# PowerToSer.net
KiCad netlist of a schematic drawn in Altium Designer
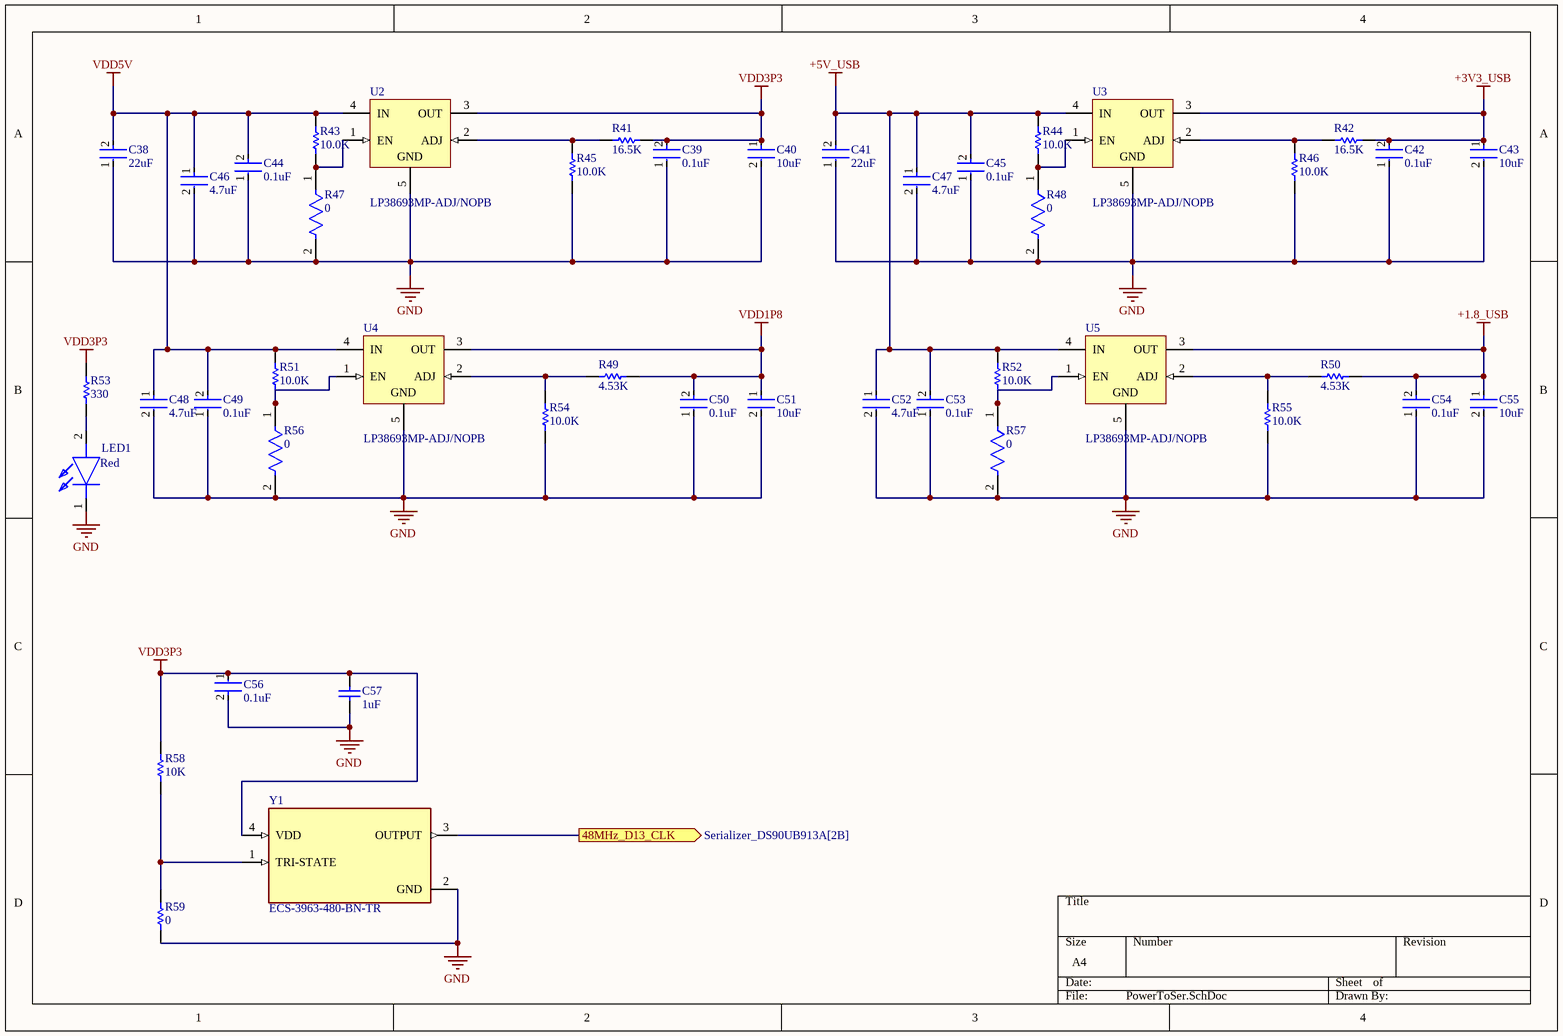
[diagram p0: PowerToSer.SchDoc]

(export (version "E")
  (design (tool "Eeschema 10.0.6"))
  (components
    (comp (ref "C38")
      (value "22uF")
      (footprint "FP-GCM32E-0_3-IPC_B")
      (description "Ceramic Capacitor for Automotive 22uF ±10% 16VDC X7R 1210 Embossed T/R")
      (fields (field (name "VOLTAGE") "16V") (field (name "TOLERANCE") "10%"))
      (libsource (lib "Altium Content Vault") (part "f23184f103b6ebe33a8c269c53dcba6"))
    )
    (comp (ref "C39")
      (value "0.1uF")
      (footprint "FP-GRM15-MFG")
      (description "CAP CER 0.1UF 16V X7R 0402")
      (fields (field (name "MANUFACTURER PART NUMBER") "GRM155R71C104KA88D") (field (name "TOLERANCE") "10%"))
      (libsource (lib "Altium Content Vault") (part "236180d848d6139a670b325ea6854c9"))
    )
    (comp (ref "C40")
      (value "10uF")
      (footprint "FP-GRM21B-0_1-IPC_C")
      (description "Chip Multilayer Ceramic Capacitors for General Purpose, 0805, 10uF, X5R, 15%, 10%, 16V")
      (fields (field (name "TOLERANCE") "10%") (field (name "VOLTAGE") "16V"))
      (libsource (lib "Altium Content Vault") (part "b4654b650e69147ec39a6b967a45e02"))
    )
    (comp (ref "C41")
      (value "22uF")
      (footprint "FP-GCM32E-0_3-IPC_B")
      (description "Ceramic Capacitor for Automotive 22uF ±10% 16VDC X7R 1210 Embossed T/R")
      (fields (field (name "VOLTAGE") "16V") (field (name "TOLERANCE") "10%"))
      (libsource (lib "Altium Content Vault") (part "f23184f103b6ebe33a8c269c53dcba6"))
    )
    (comp (ref "C42")
      (value "0.1uF")
      (footprint "FP-GRM15-MFG")
      (description "CAP CER 0.1UF 16V X7R 0402")
      (fields (field (name "MANUFACTURER PART NUMBER") "GRM155R71C104KA88D") (field (name "TOLERANCE") "10%"))
      (libsource (lib "Altium Content Vault") (part "236180d848d6139a670b325ea6854c9"))
    )
    (comp (ref "C43")
      (value "10uF")
      (footprint "FP-GRM21B-0_1-IPC_C")
      (description "Chip Multilayer Ceramic Capacitors for General Purpose, 0805, 10uF, X5R, 15%, 10%, 16V")
      (fields (field (name "TOLERANCE") "10%") (field (name "VOLTAGE") "16V"))
      (libsource (lib "Altium Content Vault") (part "b4654b650e69147ec39a6b967a45e02"))
    )
    (comp (ref "C44")
      (value "0.1uF")
      (footprint "FP-GRM15-MFG")
      (description "CAP CER 0.1UF 16V X7R 0402")
      (fields (field (name "MANUFACTURER PART NUMBER") "GRM155R71C104KA88D") (field (name "TOLERANCE") "10%"))
      (libsource (lib "Altium Content Vault") (part "236180d848d6139a670b325ea6854c9"))
    )
    (comp (ref "C45")
      (value "0.1uF")
      (footprint "FP-GRM15-MFG")
      (description "CAP CER 0.1UF 16V X7R 0402")
      (fields (field (name "MANUFACTURER PART NUMBER") "GRM155R71C104KA88D") (field (name "TOLERANCE") "10%"))
      (libsource (lib "Altium Content Vault") (part "236180d848d6139a670b325ea6854c9"))
    )
    (comp (ref "C46")
      (value "4.7uF")
      (footprint "FP-GRM21B-0_15-MFG")
      (description "CAP CER 4.7UF 16V X7R 0805")
      (fields (field (name "VOLTAGE") "16V") (field (name "TOLERANCE") "10%"))
      (libsource (lib "Altium Content Vault") (part "b4654b650e69147ec39a6b967a45e02"))
    )
    (comp (ref "C47")
      (value "4.7uF")
      (footprint "FP-GRM21B-0_15-MFG")
      (description "CAP CER 4.7UF 16V X7R 0805")
      (fields (field (name "VOLTAGE") "16V") (field (name "TOLERANCE") "10%"))
      (libsource (lib "Altium Content Vault") (part "b4654b650e69147ec39a6b967a45e02"))
    )
    (comp (ref "C48")
      (value "4.7uF")
      (footprint "FP-GRM21B-0_15-MFG")
      (description "CAP CER 4.7UF 16V X7R 0805")
      (fields (field (name "VOLTAGE") "16V") (field (name "TOLERANCE") "10%"))
      (libsource (lib "Altium Content Vault") (part "b4654b650e69147ec39a6b967a45e02"))
    )
    (comp (ref "C49")
      (value "0.1uF")
      (footprint "FP-GRM15-MFG")
      (description "CAP CER 0.1UF 16V X7R 0402")
      (fields (field (name "MANUFACTURER PART NUMBER") "GRM155R71C104KA88D") (field (name "TOLERANCE") "10%"))
      (libsource (lib "Altium Content Vault") (part "236180d848d6139a670b325ea6854c9"))
    )
    (comp (ref "C50")
      (value "0.1uF")
      (footprint "FP-GRM15-MFG")
      (description "CAP CER 0.1UF 16V X7R 0402")
      (fields (field (name "MANUFACTURER PART NUMBER") "GRM155R71C104KA88D") (field (name "TOLERANCE") "10%"))
      (libsource (lib "Altium Content Vault") (part "236180d848d6139a670b325ea6854c9"))
    )
    (comp (ref "C51")
      (value "10uF")
      (footprint "FP-GRM21B-0_1-IPC_C")
      (description "Chip Multilayer Ceramic Capacitors for General Purpose, 0805, 10uF, X5R, 15%, 10%, 16V")
      (fields (field (name "TOLERANCE") "10%") (field (name "VOLTAGE") "16V"))
      (libsource (lib "Altium Content Vault") (part "b4654b650e69147ec39a6b967a45e02"))
    )
    (comp (ref "C52")
      (value "4.7uF")
      (footprint "FP-GRM21B-0_15-MFG")
      (description "CAP CER 4.7UF 16V X7R 0805")
      (fields (field (name "VOLTAGE") "16V") (field (name "TOLERANCE") "10%"))
      (libsource (lib "Altium Content Vault") (part "b4654b650e69147ec39a6b967a45e02"))
    )
    (comp (ref "C53")
      (value "0.1uF")
      (footprint "FP-GRM15-MFG")
      (description "CAP CER 0.1UF 16V X7R 0402")
      (fields (field (name "MANUFACTURER PART NUMBER") "GRM155R71C104KA88D") (field (name "TOLERANCE") "10%"))
      (libsource (lib "Altium Content Vault") (part "236180d848d6139a670b325ea6854c9"))
    )
    (comp (ref "C54")
      (value "0.1uF")
      (footprint "FP-GRM15-MFG")
      (description "CAP CER 0.1UF 16V X7R 0402")
      (fields (field (name "MANUFACTURER PART NUMBER") "GRM155R71C104KA88D") (field (name "TOLERANCE") "10%"))
      (libsource (lib "Altium Content Vault") (part "236180d848d6139a670b325ea6854c9"))
    )
    (comp (ref "C55")
      (value "10uF")
      (footprint "FP-GRM21B-0_1-IPC_C")
      (description "Chip Multilayer Ceramic Capacitors for General Purpose, 0805, 10uF, X5R, 15%, 10%, 16V")
      (fields (field (name "TOLERANCE") "10%") (field (name "VOLTAGE") "16V"))
      (libsource (lib "Altium Content Vault") (part "b4654b650e69147ec39a6b967a45e02"))
    )
    (comp (ref "C56")
      (value "0.1uF")
      (footprint "FP-GRM15-MFG")
      (description "CAP CER 0.1UF 16V X7R 0402")
      (fields (field (name "MANUFACTURER PART NUMBER") "GRM155R71C104KA88D") (field (name "TOLERANCE") "10%"))
      (libsource (lib "Altium Content Vault") (part "236180d848d6139a670b325ea6854c9"))
    )
    (comp (ref "C57")
      (value "1uF")
      (footprint "CAPC1608X90X35ML10T15")
      (fields (field (name "MANUFACTURER") "Murata") (field (name "PART NUMBER") "GRM188R71E105KA12D"))
      (libsource (lib "Altium Content Vault") (part "CAP"))
    )
    (comp (ref "LED1")
      (value "Red")
      (footprint "SerDes_Eval_Board_Footprints:LEDC1608X55N")
      (description "LED")
      (fields
        (field (name "MANUFACTURER_PART_NUMBER") "LTST-C191KRKT")
        (field (name "MOUSER PART NUMBER") "859-LTST-C191KRKT")
      )
      (libsource (lib "SerDes_Eval") (part "LTST-C191KRKT"))
    )
    (comp (ref "R41")
      (value "16.5K")
      (footprint "RESC1608X55X30LL15T15")
      (fields (field (name "MANUFACTURER") "Panasonic") (field (name "PART NUMBER") "ERJ-3EKF1652V"))
      (libsource (lib "Altium Content Vault") (part "RES"))
    )
    (comp (ref "R42")
      (value "16.5K")
      (footprint "RESC1608X55X30LL15T15")
      (fields (field (name "MANUFACTURER") "Panasonic") (field (name "PART NUMBER") "ERJ-3EKF1652V"))
      (libsource (lib "Altium Content Vault") (part "RES"))
    )
    (comp (ref "R43")
      (value "10.0K")
      (footprint "RESC1609X55X30LL15T15")
      (description "Chip Resistor, 10 KOhm, +/- 1%, 0.1 W, -55 to 155 degC, 0603 (1608 Metric), RoHS, Tape and Reel")
      (fields (field (name "TOLERANCE") "1%") (field (name "MANUFACTURER") "Panasonic"))
      (libsource (lib "Altium Content Vault") (part "RES-2"))
    )
    (comp (ref "R44")
      (value "10.0K")
      (footprint "RESC1609X55X30LL15T15")
      (description "Chip Resistor, 10 KOhm, +/- 1%, 0.1 W, -55 to 155 degC, 0603 (1608 Metric), RoHS, Tape and Reel")
      (fields (field (name "TOLERANCE") "1%") (field (name "MANUFACTURER") "Panasonic"))
      (libsource (lib "Altium Content Vault") (part "RES-2"))
    )
    (comp (ref "R45")
      (value "10.0K")
      (footprint "RESC1609X55X30LL15T15")
      (description "Chip Resistor, 10 KOhm, +/- 1%, 0.1 W, -55 to 155 degC, 0603 (1608 Metric), RoHS, Tape and Reel")
      (fields (field (name "TOLERANCE") "1%") (field (name "MANUFACTURER") "Panasonic"))
      (libsource (lib "Altium Content Vault") (part "RES-2"))
    )
    (comp (ref "R46")
      (value "10.0K")
      (footprint "RESC1609X55X30LL15T15")
      (description "Chip Resistor, 10 KOhm, +/- 1%, 0.1 W, -55 to 155 degC, 0603 (1608 Metric), RoHS, Tape and Reel")
      (fields (field (name "TOLERANCE") "1%") (field (name "MANUFACTURER") "Panasonic"))
      (libsource (lib "Altium Content Vault") (part "RES-2"))
    )
    (comp (ref "R47")
      (value "0")
      (footprint "FP-ERJ-3GEY0R00V-MFG")
      (description "RES SMD 0 OHM JUMPER 1/10W 0603")
      (fields (field (name "TOLERANCE") "5%") (field (name "MANUFACTURER PART NUMBER") "ERJ-3GEY0R00V"))
      (libsource (lib "Altium Content Vault") (part "1029c3af85768c4190bb7ad29bc67b5"))
    )
    (comp (ref "R48")
      (value "0")
      (footprint "FP-ERJ-3GEY0R00V-MFG")
      (description "RES SMD 0 OHM JUMPER 1/10W 0603")
      (fields (field (name "TOLERANCE") "5%") (field (name "MANUFACTURER PART NUMBER") "ERJ-3GEY0R00V"))
      (libsource (lib "Altium Content Vault") (part "1029c3af85768c4190bb7ad29bc67b5"))
    )
    (comp (ref "R49")
      (value "4.53K")
      (footprint "RESC1608X55X30ML15T15")
      (fields (field (name "PART NUMBER") "ERJ-3EKF4531V") (field (name "MANUFACTURER") "Panasonic"))
      (libsource (lib "Altium Content Vault") (part "RES"))
    )
    (comp (ref "R50")
      (value "4.53K")
      (footprint "RESC1608X55X30ML15T15")
      (fields (field (name "PART NUMBER") "ERJ-3EKF4531V") (field (name "MANUFACTURER") "Panasonic"))
      (libsource (lib "Altium Content Vault") (part "RES"))
    )
    (comp (ref "R51")
      (value "10.0K")
      (footprint "RESC1609X55X30LL15T15")
      (description "Chip Resistor, 10 KOhm, +/- 1%, 0.1 W, -55 to 155 degC, 0603 (1608 Metric), RoHS, Tape and Reel")
      (fields (field (name "TOLERANCE") "1%") (field (name "MANUFACTURER") "Panasonic"))
      (libsource (lib "Altium Content Vault") (part "RES-2"))
    )
    (comp (ref "R52")
      (value "10.0K")
      (footprint "RESC1609X55X30LL15T15")
      (description "Chip Resistor, 10 KOhm, +/- 1%, 0.1 W, -55 to 155 degC, 0603 (1608 Metric), RoHS, Tape and Reel")
      (fields (field (name "TOLERANCE") "1%") (field (name "MANUFACTURER") "Panasonic"))
      (libsource (lib "Altium Content Vault") (part "RES-2"))
    )
    (comp (ref "R53")
      (value "330")
      (footprint "RESC1005X40X25ML05T05")
      (fields (field (name "MANUFACTURER") "Panasonic") (field (name "PART NUMBER") "ERJ2RKF3300X"))
      (libsource (lib "Altium Content Vault") (part "RES"))
    )
    (comp (ref "R54")
      (value "10.0K")
      (footprint "RESC1609X55X30LL15T15")
      (description "Chip Resistor, 10 KOhm, +/- 1%, 0.1 W, -55 to 155 degC, 0603 (1608 Metric), RoHS, Tape and Reel")
      (fields (field (name "TOLERANCE") "1%") (field (name "MANUFACTURER") "Panasonic"))
      (libsource (lib "Altium Content Vault") (part "RES-2"))
    )
    (comp (ref "R55")
      (value "10.0K")
      (footprint "RESC1609X55X30LL15T15")
      (description "Chip Resistor, 10 KOhm, +/- 1%, 0.1 W, -55 to 155 degC, 0603 (1608 Metric), RoHS, Tape and Reel")
      (fields (field (name "TOLERANCE") "1%") (field (name "MANUFACTURER") "Panasonic"))
      (libsource (lib "Altium Content Vault") (part "RES-2"))
    )
    (comp (ref "R56")
      (value "0")
      (footprint "FP-ERJ-3GEY0R00V-MFG")
      (description "RES SMD 0 OHM JUMPER 1/10W 0603")
      (fields (field (name "TOLERANCE") "5%") (field (name "MANUFACTURER PART NUMBER") "ERJ-3GEY0R00V"))
      (libsource (lib "Altium Content Vault") (part "1029c3af85768c4190bb7ad29bc67b5"))
    )
    (comp (ref "R57")
      (value "0")
      (footprint "FP-ERJ-3GEY0R00V-MFG")
      (description "RES SMD 0 OHM JUMPER 1/10W 0603")
      (fields (field (name "TOLERANCE") "5%") (field (name "MANUFACTURER PART NUMBER") "ERJ-3GEY0R00V"))
      (libsource (lib "Altium Content Vault") (part "1029c3af85768c4190bb7ad29bc67b5"))
    )
    (comp (ref "R58")
      (value "10K")
      (footprint "RESC1005X40X25ML05T05")
      (fields (field (name "PART NUMBER") "ERJ-2GEJ103X") (field (name "MANUFACTURER") "Panasonic"))
      (libsource (lib "Altium Content Vault") (part "RES"))
    )
    (comp (ref "R59")
      (value "0")
      (footprint "RESC1005X40X25LL05T05")
      (description "Chip Resistor, 0 Ohm, 0.1 W, -55 to 155 degC, 0402 (1005 Metric), RoHS, Tape and Reel")
      (fields (field (name "MANUFACTURER") "Panasonic") (field (name "TOLERANCE") "5%"))
      (libsource (lib "Altium Content Vault") (part "RES-2"))
    )
    (comp (ref "U2")
      (value "LP38693MP-ADJ/NOPB")
      (footprint "NDC0005A_N")
      (fields (field (name "MANUFACTURER") "Texas Instruments"))
      (libsource (lib "Altium Content Vault") (part "PM-REG-LP38693ADJ-SOT5"))
    )
    (comp (ref "U3")
      (value "LP38693MP-ADJ/NOPB")
      (footprint "NDC0005A_N")
      (fields (field (name "MANUFACTURER") "Texas Instruments"))
      (libsource (lib "Altium Content Vault") (part "PM-REG-LP38693ADJ-SOT5"))
    )
    (comp (ref "U4")
      (value "LP38693MP-ADJ/NOPB")
      (footprint "NDC0005A_N")
      (fields (field (name "MANUFACTURER") "Texas Instruments"))
      (libsource (lib "Altium Content Vault") (part "PM-REG-LP38693ADJ-SOT5"))
    )
    (comp (ref "U5")
      (value "LP38693MP-ADJ/NOPB")
      (footprint "NDC0005A_N")
      (fields (field (name "MANUFACTURER") "Texas Instruments"))
      (libsource (lib "Altium Content Vault") (part "PM-REG-LP38693ADJ-SOT5"))
    )
    (comp (ref "Y1")
      (value "ECS-3963-480-BN-TR")
      (footprint "SerDes_Eval_Board_Footprints:OSC_ECS-3963-480-BN-TR")
      (description "miniature SMD crystal controlled oscillators")
      (libsource (lib "SerDes_Eval") (part "ECS-3963-480-BN-TR"))
    )
  )
  (nets
    (net (code "1") (name "+1.8_USB") (class "Default")
      (node (ref "C54") (pin "2") (pinfunction "2_2") (pintype "passive"))
      (node (ref "C55") (pin "1") (pinfunction "1_1") (pintype "passive"))
      (node (ref "R50") (pin "2") (pinfunction "2_2") (pintype "passive"))
      (node (ref "U5") (pin "3") (pinfunction "OUT_3") (pintype "power_in"))
    )
    (net (code "2") (name "+3V3_USB") (class "Default")
      (node (ref "C42") (pin "2") (pinfunction "2_2") (pintype "passive"))
      (node (ref "C43") (pin "1") (pinfunction "1_1") (pintype "passive"))
      (node (ref "R42") (pin "2") (pinfunction "2_2") (pintype "passive"))
      (node (ref "U3") (pin "3") (pinfunction "OUT_3") (pintype "power_in"))
    )
    (net (code "3") (name "+5V_USB") (class "Default")
      (node (ref "C41") (pin "2") (pinfunction "2_2") (pintype "passive"))
      (node (ref "C45") (pin "2") (pinfunction "2_2") (pintype "passive"))
      (node (ref "C47") (pin "1") (pinfunction "1_1") (pintype "passive"))
      (node (ref "C52") (pin "1") (pinfunction "1_1") (pintype "passive"))
      (node (ref "C53") (pin "2") (pinfunction "2_2") (pintype "passive"))
      (node (ref "R44") (pin "1") (pinfunction "1_1") (pintype "passive"))
      (node (ref "R52") (pin "1") (pinfunction "1_1") (pintype "passive"))
      (node (ref "U3") (pin "4") (pinfunction "IN_4") (pintype "power_in"))
      (node (ref "U5") (pin "4") (pinfunction "IN_4") (pintype "power_in"))
    )
    (net (code "4") (name "/48MHz_D13_CLK") (class "Default")
      (node (ref "Y1") (pin "3") (pinfunction "OUTPUT_3") (pintype "output"))
    )
    (net (code "5") (name "GND") (class "Default")
      (node (ref "C38") (pin "1") (pinfunction "1_1") (pintype "passive"))
      (node (ref "C39") (pin "1") (pinfunction "1_1") (pintype "passive"))
      (node (ref "C40") (pin "2") (pinfunction "2_2") (pintype "passive"))
      (node (ref "C41") (pin "1") (pinfunction "1_1") (pintype "passive"))
      (node (ref "C42") (pin "1") (pinfunction "1_1") (pintype "passive"))
      (node (ref "C43") (pin "2") (pinfunction "2_2") (pintype "passive"))
      (node (ref "C44") (pin "1") (pinfunction "1_1") (pintype "passive"))
      (node (ref "C45") (pin "1") (pinfunction "1_1") (pintype "passive"))
      (node (ref "C46") (pin "2") (pinfunction "2_2") (pintype "passive"))
      (node (ref "C47") (pin "2") (pinfunction "2_2") (pintype "passive"))
      (node (ref "C48") (pin "2") (pinfunction "2_2") (pintype "passive"))
      (node (ref "C49") (pin "1") (pinfunction "1_1") (pintype "passive"))
      (node (ref "C50") (pin "1") (pinfunction "1_1") (pintype "passive"))
      (node (ref "C51") (pin "2") (pinfunction "2_2") (pintype "passive"))
      (node (ref "C52") (pin "2") (pinfunction "2_2") (pintype "passive"))
      (node (ref "C53") (pin "1") (pinfunction "1_1") (pintype "passive"))
      (node (ref "C54") (pin "1") (pinfunction "1_1") (pintype "passive"))
      (node (ref "C55") (pin "2") (pinfunction "2_2") (pintype "passive"))
      (node (ref "C56") (pin "2") (pinfunction "2_2") (pintype "passive"))
      (node (ref "C57") (pin "2") (pinfunction "2_2") (pintype "passive"))
      (node (ref "LED1") (pin "1") (pinfunction "K_1") (pintype "passive"))
      (node (ref "R45") (pin "2") (pinfunction "2_2") (pintype "passive"))
      (node (ref "R46") (pin "2") (pinfunction "2_2") (pintype "passive"))
      (node (ref "R47") (pin "2") (pinfunction "2_2") (pintype "passive"))
      (node (ref "R48") (pin "2") (pinfunction "2_2") (pintype "passive"))
      (node (ref "R54") (pin "2") (pinfunction "2_2") (pintype "passive"))
      (node (ref "R55") (pin "2") (pinfunction "2_2") (pintype "passive"))
      (node (ref "R56") (pin "2") (pinfunction "2_2") (pintype "passive"))
      (node (ref "R57") (pin "2") (pinfunction "2_2") (pintype "passive"))
      (node (ref "R59") (pin "2") (pinfunction "2_2") (pintype "passive"))
      (node (ref "U2") (pin "5") (pinfunction "GND_5") (pintype "power_in"))
      (node (ref "U3") (pin "5") (pinfunction "GND_5") (pintype "power_in"))
      (node (ref "U4") (pin "5") (pinfunction "GND_5") (pintype "power_in"))
      (node (ref "U5") (pin "5") (pinfunction "GND_5") (pintype "power_in"))
      (node (ref "Y1") (pin "2") (pinfunction "GND_2") (pintype "power_in"))
    )
    (net (code "6") (name "Net-(LED1-A)") (class "Default")
      (node (ref "LED1") (pin "2") (pinfunction "A_2") (pintype "passive"))
      (node (ref "R53") (pin "2") (pinfunction "2_2") (pintype "passive"))
    )
    (net (code "7") (name "Net-(U2-ADJ)") (class "Default")
      (node (ref "R41") (pin "1") (pinfunction "1_1") (pintype "passive"))
      (node (ref "R45") (pin "1") (pinfunction "1_1") (pintype "passive"))
      (node (ref "U2") (pin "2") (pinfunction "ADJ_2") (pintype "input"))
    )
    (net (code "8") (name "Net-(U2-EN)") (class "Default")
      (node (ref "R43") (pin "2") (pinfunction "2_2") (pintype "passive"))
      (node (ref "R47") (pin "1") (pinfunction "1_1") (pintype "passive"))
      (node (ref "U2") (pin "1") (pinfunction "EN_1") (pintype "input"))
    )
    (net (code "9") (name "Net-(U3-ADJ)") (class "Default")
      (node (ref "R42") (pin "1") (pinfunction "1_1") (pintype "passive"))
      (node (ref "R46") (pin "1") (pinfunction "1_1") (pintype "passive"))
      (node (ref "U3") (pin "2") (pinfunction "ADJ_2") (pintype "input"))
    )
    (net (code "10") (name "Net-(U3-EN)") (class "Default")
      (node (ref "R44") (pin "2") (pinfunction "2_2") (pintype "passive"))
      (node (ref "R48") (pin "1") (pinfunction "1_1") (pintype "passive"))
      (node (ref "U3") (pin "1") (pinfunction "EN_1") (pintype "input"))
    )
    (net (code "11") (name "Net-(U4-ADJ)") (class "Default")
      (node (ref "R49") (pin "1") (pinfunction "1_1") (pintype "passive"))
      (node (ref "R54") (pin "1") (pinfunction "1_1") (pintype "passive"))
      (node (ref "U4") (pin "2") (pinfunction "ADJ_2") (pintype "input"))
    )
    (net (code "12") (name "Net-(U4-EN)") (class "Default")
      (node (ref "R51") (pin "2") (pinfunction "2_2") (pintype "passive"))
      (node (ref "R56") (pin "1") (pinfunction "1_1") (pintype "passive"))
      (node (ref "U4") (pin "1") (pinfunction "EN_1") (pintype "input"))
    )
    (net (code "13") (name "Net-(U5-ADJ)") (class "Default")
      (node (ref "R50") (pin "1") (pinfunction "1_1") (pintype "passive"))
      (node (ref "R55") (pin "1") (pinfunction "1_1") (pintype "passive"))
      (node (ref "U5") (pin "2") (pinfunction "ADJ_2") (pintype "input"))
    )
    (net (code "14") (name "Net-(U5-EN)") (class "Default")
      (node (ref "R52") (pin "2") (pinfunction "2_2") (pintype "passive"))
      (node (ref "R57") (pin "1") (pinfunction "1_1") (pintype "passive"))
      (node (ref "U5") (pin "1") (pinfunction "EN_1") (pintype "input"))
    )
    (net (code "15") (name "Net-(Y1-TRI-STATE)") (class "Default")
      (node (ref "R58") (pin "2") (pinfunction "2_2") (pintype "passive"))
      (node (ref "R59") (pin "1") (pinfunction "1_1") (pintype "passive"))
      (node (ref "Y1") (pin "1") (pinfunction "TRI-STATE_1") (pintype "input"))
    )
    (net (code "16") (name "VDD1P8") (class "Default")
      (node (ref "C50") (pin "2") (pinfunction "2_2") (pintype "passive"))
      (node (ref "C51") (pin "1") (pinfunction "1_1") (pintype "passive"))
      (node (ref "R49") (pin "2") (pinfunction "2_2") (pintype "passive"))
      (node (ref "U4") (pin "3") (pinfunction "OUT_3") (pintype "power_in"))
    )
    (net (code "17") (name "VDD3P3") (class "Default")
      (node (ref "C39") (pin "2") (pinfunction "2_2") (pintype "passive"))
      (node (ref "C40") (pin "1") (pinfunction "1_1") (pintype "passive"))
      (node (ref "C56") (pin "1") (pinfunction "1_1") (pintype "passive"))
      (node (ref "C57") (pin "1") (pinfunction "1_1") (pintype "passive"))
      (node (ref "R41") (pin "2") (pinfunction "2_2") (pintype "passive"))
      (node (ref "R53") (pin "1") (pinfunction "1_1") (pintype "passive"))
      (node (ref "R58") (pin "1") (pinfunction "1_1") (pintype "passive"))
      (node (ref "U2") (pin "3") (pinfunction "OUT_3") (pintype "power_in"))
      (node (ref "Y1") (pin "4") (pinfunction "VDD_4") (pintype "input"))
    )
    (net (code "18") (name "VDD5V") (class "Default")
      (node (ref "C38") (pin "2") (pinfunction "2_2") (pintype "passive"))
      (node (ref "C44") (pin "2") (pinfunction "2_2") (pintype "passive"))
      (node (ref "C46") (pin "1") (pinfunction "1_1") (pintype "passive"))
      (node (ref "C48") (pin "1") (pinfunction "1_1") (pintype "passive"))
      (node (ref "C49") (pin "2") (pinfunction "2_2") (pintype "passive"))
      (node (ref "R43") (pin "1") (pinfunction "1_1") (pintype "passive"))
      (node (ref "R51") (pin "1") (pinfunction "1_1") (pintype "passive"))
      (node (ref "U2") (pin "4") (pinfunction "IN_4") (pintype "power_in"))
      (node (ref "U4") (pin "4") (pinfunction "IN_4") (pintype "power_in"))
    )
  )
)
